# power_supply.net
KiCad netlist of a schematic drawn in Altium Designer
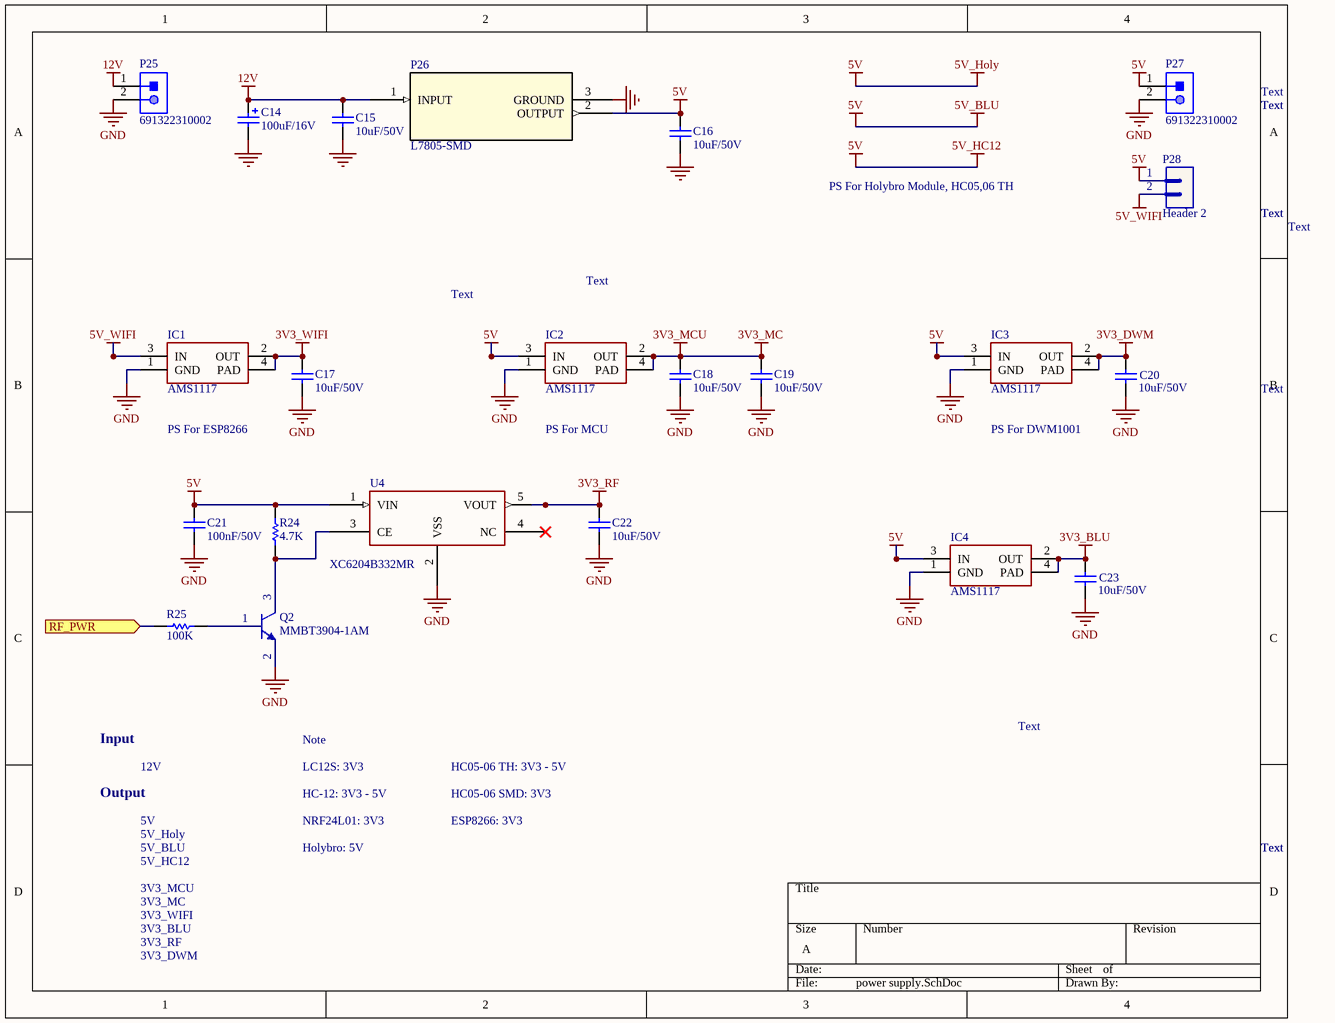
[diagram p0: power supply.SchDoc]

(export (version "E")
  (design (tool "Eeschema 10.0.6"))
  (components
    (comp (ref "C14")
      (value "100uF/16V")
      (footprint "CAP-SM-AL-SIZE-D-D6L6")
      (description "CAP ALUM 100UF 20% 16V SMD")
      (fields
        (field (name "MANUFACTURER") "Nichicon")
        (field (name "MANUFACTURER PART NUMBER") "UWX1C101MCL1GB")
      )
      (libsource (lib "Capacitor") (part "Cap-Al-100uF-16V-D6L5"))
    )
    (comp (ref "C15")
      (value "10uF/50V")
      (footprint "CAP-SM-0805")
      (description "CAP CER 10UF 50V X5R 0805")
      (fields
        (field (name "MANUFACTURER") "Yageo")
        (field (name "MANUFACTURER PART NUMBER") "CC0805KKX5R9BB106")
      )
      (libsource (lib "Capacitor") (part "Cap-10uF-50V-0805"))
    )
    (comp (ref "C16")
      (value "10uF/50V")
      (footprint "CAP-SM-0805")
      (description "CAP CER 10UF 50V X5R 0805")
      (fields
        (field (name "MANUFACTURER") "Yageo")
        (field (name "MANUFACTURER PART NUMBER") "CC0805KKX5R9BB106")
      )
      (libsource (lib "Capacitor") (part "Cap-10uF-50V-0805"))
    )
    (comp (ref "C17")
      (value "10uF/50V")
      (footprint "CAP-SM-0805")
      (description "CAP CER 10UF 50V X5R 0805")
      (fields
        (field (name "MANUFACTURER") "Yageo")
        (field (name "MANUFACTURER PART NUMBER") "CC0805KKX5R9BB106")
      )
      (libsource (lib "Capacitor") (part "Cap-10uF-50V-0805"))
    )
    (comp (ref "C18")
      (value "10uF/50V")
      (footprint "CAP-SM-0805")
      (description "CAP CER 10UF 50V X5R 0805")
      (fields
        (field (name "MANUFACTURER") "Yageo")
        (field (name "MANUFACTURER PART NUMBER") "CC0805KKX5R9BB106")
      )
      (libsource (lib "Capacitor") (part "Cap-10uF-50V-0805"))
    )
    (comp (ref "C19")
      (value "10uF/50V")
      (footprint "CAP-SM-0805")
      (description "CAP CER 10UF 50V X5R 0805")
      (fields
        (field (name "MANUFACTURER") "Yageo")
        (field (name "MANUFACTURER PART NUMBER") "CC0805KKX5R9BB106")
      )
      (libsource (lib "Capacitor") (part "Cap-10uF-50V-0805"))
    )
    (comp (ref "C20")
      (value "10uF/50V")
      (footprint "CAP-SM-0805")
      (description "CAP CER 10UF 50V X5R 0805")
      (fields
        (field (name "MANUFACTURER") "Yageo")
        (field (name "MANUFACTURER PART NUMBER") "CC0805KKX5R9BB106")
      )
      (libsource (lib "Capacitor") (part "Cap-10uF-50V-0805"))
    )
    (comp (ref "C21")
      (value "100nF/50V")
      (footprint "CAP-SM-0805")
      (description "CAP CER 0.1UF 50V Y5V 0805")
      (fields
        (field (name "MANUFACTURER") "Samsung Electro-Mechanics")
        (field (name "MANUFACTURER PART NUMBER") "CL21F104ZBCNNNC")
      )
      (libsource (lib "Capacitor") (part "Cap-100nF-50V-0805"))
    )
    (comp (ref "C22")
      (value "10uF/50V")
      (footprint "CAP-SM-0805")
      (description "CAP CER 10UF 50V X5R 0805")
      (fields
        (field (name "MANUFACTURER") "Yageo")
        (field (name "MANUFACTURER PART NUMBER") "CC0805KKX5R9BB106")
      )
      (libsource (lib "Capacitor") (part "Cap-10uF-50V-0805"))
    )
    (comp (ref "C23")
      (value "10uF/50V")
      (footprint "CAP-SM-0805")
      (description "CAP CER 10UF 50V X5R 0805")
      (fields
        (field (name "MANUFACTURER") "Yageo")
        (field (name "MANUFACTURER PART NUMBER") "CC0805KKX5R9BB106")
      )
      (libsource (lib "Capacitor") (part "Cap-10uF-50V-0805"))
    )
    (comp (ref "IC1")
      (value "AMS1117")
      (footprint "SOT223")
      (description "Available in 1.8V, 2.5V, 2.85V, 3.3V, 5V, and  Adjustable Versions")
      (libsource (lib "PI") (part "AMS1117"))
    )
    (comp (ref "IC2")
      (value "AMS1117")
      (footprint "SOT223")
      (description "Available in 1.8V, 2.5V, 2.85V, 3.3V, 5V, and  Adjustable Versions")
      (libsource (lib "PI") (part "AMS1117"))
    )
    (comp (ref "IC3")
      (value "AMS1117")
      (footprint "SOT223")
      (description "Available in 1.8V, 2.5V, 2.85V, 3.3V, 5V, and  Adjustable Versions")
      (libsource (lib "PI") (part "AMS1117"))
    )
    (comp (ref "IC4")
      (value "AMS1117")
      (footprint "SOT223")
      (description "Available in 1.8V, 2.5V, 2.85V, 3.3V, 5V, and  Adjustable Versions")
      (libsource (lib "PI") (part "AMS1117"))
    )
    (comp (ref "P25")
      (value "691322310002")
      (footprint "691322310002")
      (description "WR-TBL Serie 322 Horizontal PCB Header, Pluggable, pitch 3.81mm, 2p")
      (fields (field (name "PUBLISHER") "Wurth Elektronik"))
      (libsource (lib "691101710002_Altium_WR-TBL_rev19a") (part "691322310002"))
    )
    (comp (ref "P26") (value "L7805-SMD") (footprint "L7805") (libsource (lib "Schlib1") (part "L7805")))
    (comp (ref "P27")
      (value "691322310002")
      (footprint "691322310002")
      (description "WR-TBL Serie 322 Horizontal PCB Header, Pluggable, pitch 3.81mm, 2p")
      (fields (field (name "PUBLISHER") "Wurth Elektronik"))
      (libsource (lib "691101710002_Altium_WR-TBL_rev19a") (part "691322310002"))
    )
    (comp (ref "P28")
      (value "Header 2")
      (footprint "JP2")
      (description "Header, 2-Pin")
      (fields (field (name "PUBLISHER") "Altium Limited"))
      (libsource (lib "PIF_C16_2_lib") (part "Header 2"))
    )
    (comp (ref "Q2")
      (value "MMBT3904-1AM")
      (footprint "SOT23_NEX")
      (libsource (lib "BJT") (part "MMBT3904-1AM"))
    )
    (comp (ref "R24")
      (value "4.7K")
      (footprint "Resistor:RES-SM-0805")
      (description "RES SMD 4.7K OHM 5% 1/8W 0805")
      (fields
        (field (name "MANUFACTURER") "Yageo")
        (field (name "MANUFACTURER PART NUMBER") "RC0805JR-074K7L")
      )
      (libsource (lib "Resistor") (part "Res-4.7K-0805"))
    )
    (comp (ref "R25")
      (value "100K")
      (footprint "Resistor:RES-SM-0805")
      (description "RES 0 OHM JUMPER 0805")
      (fields
        (field (name "MANUFACTURER") "Vishay Dale")
        (field (name "MANUFACTURER PART NUMBER") "WSL080500000ZEA9")
      )
      (libsource (lib "Resistor") (part "Res-100K-0805"))
    )
    (comp (ref "U4")
      (value "XC6204B332MR")
      (footprint "XC6204/05_SOT-00")
      (fields (field (name "COPYRIGHT") "Copyright (C) 2018 Accelerated Designs. All rights reserved"))
      (libsource (lib "PI") (part "XC6204B332MR"))
    )
  )
  (nets
    (net (code "1") (name "/RF_PWR") (class "Default")
      (node (ref "R25") (pin "1") (pinfunction "1_1") (pintype "passive"))
    )
    (net (code "2") (name "3V3_BLU") (class "Default")
      (node (ref "C23") (pin "2") (pinfunction "2_2") (pintype "passive"))
      (node (ref "IC4") (pin "2") (pinfunction "OUT_2") (pintype "passive"))
      (node (ref "IC4") (pin "4") (pinfunction "PAD_4") (pintype "passive"))
    )
    (net (code "3") (name "3V3_DWM") (class "Default")
      (node (ref "C20") (pin "2") (pinfunction "2_2") (pintype "passive"))
      (node (ref "IC3") (pin "2") (pinfunction "OUT_2") (pintype "passive"))
      (node (ref "IC3") (pin "4") (pinfunction "PAD_4") (pintype "passive"))
    )
    (net (code "4") (name "3V3_MC") (class "Default")
      (node (ref "C18") (pin "2") (pinfunction "2_2") (pintype "passive"))
      (node (ref "C19") (pin "2") (pinfunction "2_2") (pintype "passive"))
      (node (ref "IC2") (pin "2") (pinfunction "OUT_2") (pintype "passive"))
      (node (ref "IC2") (pin "4") (pinfunction "PAD_4") (pintype "passive"))
    )
    (net (code "5") (name "3V3_RF") (class "Default")
      (node (ref "C22") (pin "2") (pinfunction "2_2") (pintype "passive"))
      (node (ref "U4") (pin "5") (pinfunction "VOUT_5") (pintype "output"))
    )
    (net (code "6") (name "3V3_WIFI") (class "Default")
      (node (ref "C17") (pin "2") (pinfunction "2_2") (pintype "passive"))
      (node (ref "IC1") (pin "2") (pinfunction "OUT_2") (pintype "passive"))
      (node (ref "IC1") (pin "4") (pinfunction "PAD_4") (pintype "passive"))
    )
    (net (code "7") (name "5V") (class "Default")
      (node (ref "C16") (pin "2") (pinfunction "2_2") (pintype "passive"))
      (node (ref "C21") (pin "2") (pinfunction "2_2") (pintype "passive"))
      (node (ref "IC2") (pin "3") (pinfunction "IN_3") (pintype "passive"))
      (node (ref "IC3") (pin "3") (pinfunction "IN_3") (pintype "passive"))
      (node (ref "IC4") (pin "3") (pinfunction "IN_3") (pintype "passive"))
      (node (ref "P26") (pin "2") (pinfunction "OUTPUT_2") (pintype "output"))
      (node (ref "P27") (pin "1") (pinfunction "1_1") (pintype "passive"))
      (node (ref "P28") (pin "1") (pinfunction "1_1") (pintype "passive"))
      (node (ref "R24") (pin "2") (pinfunction "2_2") (pintype "passive"))
      (node (ref "U4") (pin "1") (pinfunction "VIN_1") (pintype "input"))
    )
    (net (code "8") (name "5V_WIFI") (class "Default")
      (node (ref "IC1") (pin "3") (pinfunction "IN_3") (pintype "passive"))
      (node (ref "P28") (pin "2") (pinfunction "2_2") (pintype "passive"))
    )
    (net (code "9") (name "12V") (class "Default")
      (node (ref "C14") (pin "1") (pinfunction "1_1") (pintype "passive"))
      (node (ref "C15") (pin "2") (pinfunction "2_2") (pintype "passive"))
      (node (ref "P25") (pin "1") (pinfunction "1_1") (pintype "passive"))
      (node (ref "P26") (pin "1") (pinfunction "INPUT_1") (pintype "input"))
    )
    (net (code "10") (name "GND") (class "Default")
      (node (ref "C14") (pin "2") (pinfunction "2_2") (pintype "passive"))
      (node (ref "C15") (pin "1") (pinfunction "1_1") (pintype "passive"))
      (node (ref "C16") (pin "1") (pinfunction "1_1") (pintype "passive"))
      (node (ref "C17") (pin "1") (pinfunction "1_1") (pintype "passive"))
      (node (ref "C18") (pin "1") (pinfunction "1_1") (pintype "passive"))
      (node (ref "C19") (pin "1") (pinfunction "1_1") (pintype "passive"))
      (node (ref "C20") (pin "1") (pinfunction "1_1") (pintype "passive"))
      (node (ref "C21") (pin "1") (pinfunction "1_1") (pintype "passive"))
      (node (ref "C22") (pin "1") (pinfunction "1_1") (pintype "passive"))
      (node (ref "C23") (pin "1") (pinfunction "1_1") (pintype "passive"))
      (node (ref "IC1") (pin "1") (pinfunction "GND_1") (pintype "passive"))
      (node (ref "IC2") (pin "1") (pinfunction "GND_1") (pintype "passive"))
      (node (ref "IC3") (pin "1") (pinfunction "GND_1") (pintype "passive"))
      (node (ref "IC4") (pin "1") (pinfunction "GND_1") (pintype "passive"))
      (node (ref "P25") (pin "2") (pinfunction "2_2") (pintype "passive"))
      (node (ref "P26") (pin "3") (pinfunction "GROUND_3") (pintype "passive"))
      (node (ref "P27") (pin "2") (pinfunction "2_2") (pintype "passive"))
      (node (ref "Q2") (pin "2") (pinfunction "E_2") (pintype "passive"))
      (node (ref "U4") (pin "2") (pinfunction "VSS_2") (pintype "passive"))
    )
    (net (code "11") (name "Net-(Q2-B)") (class "Default")
      (node (ref "Q2") (pin "1") (pinfunction "B_1") (pintype "passive"))
      (node (ref "R25") (pin "2") (pinfunction "2_2") (pintype "passive"))
    )
    (net (code "12") (name "Net-(Q2-C)") (class "Default")
      (node (ref "Q2") (pin "3") (pinfunction "C_3") (pintype "passive"))
      (node (ref "R24") (pin "1") (pinfunction "1_1") (pintype "passive"))
      (node (ref "U4") (pin "3") (pinfunction "CE_3") (pintype "passive"))
    )
    (net (code "13") (name "unconnected-(U4-NC-Pad4)") (class "Default")
      (node (ref "U4") (pin "4") (pinfunction "NC_4") (pintype "passive+no_connect"))
    )
  )
)
